# 06_-_CPU_-_HDMI_LVDS.net
KiCad netlist of a schematic drawn in Altium Designer
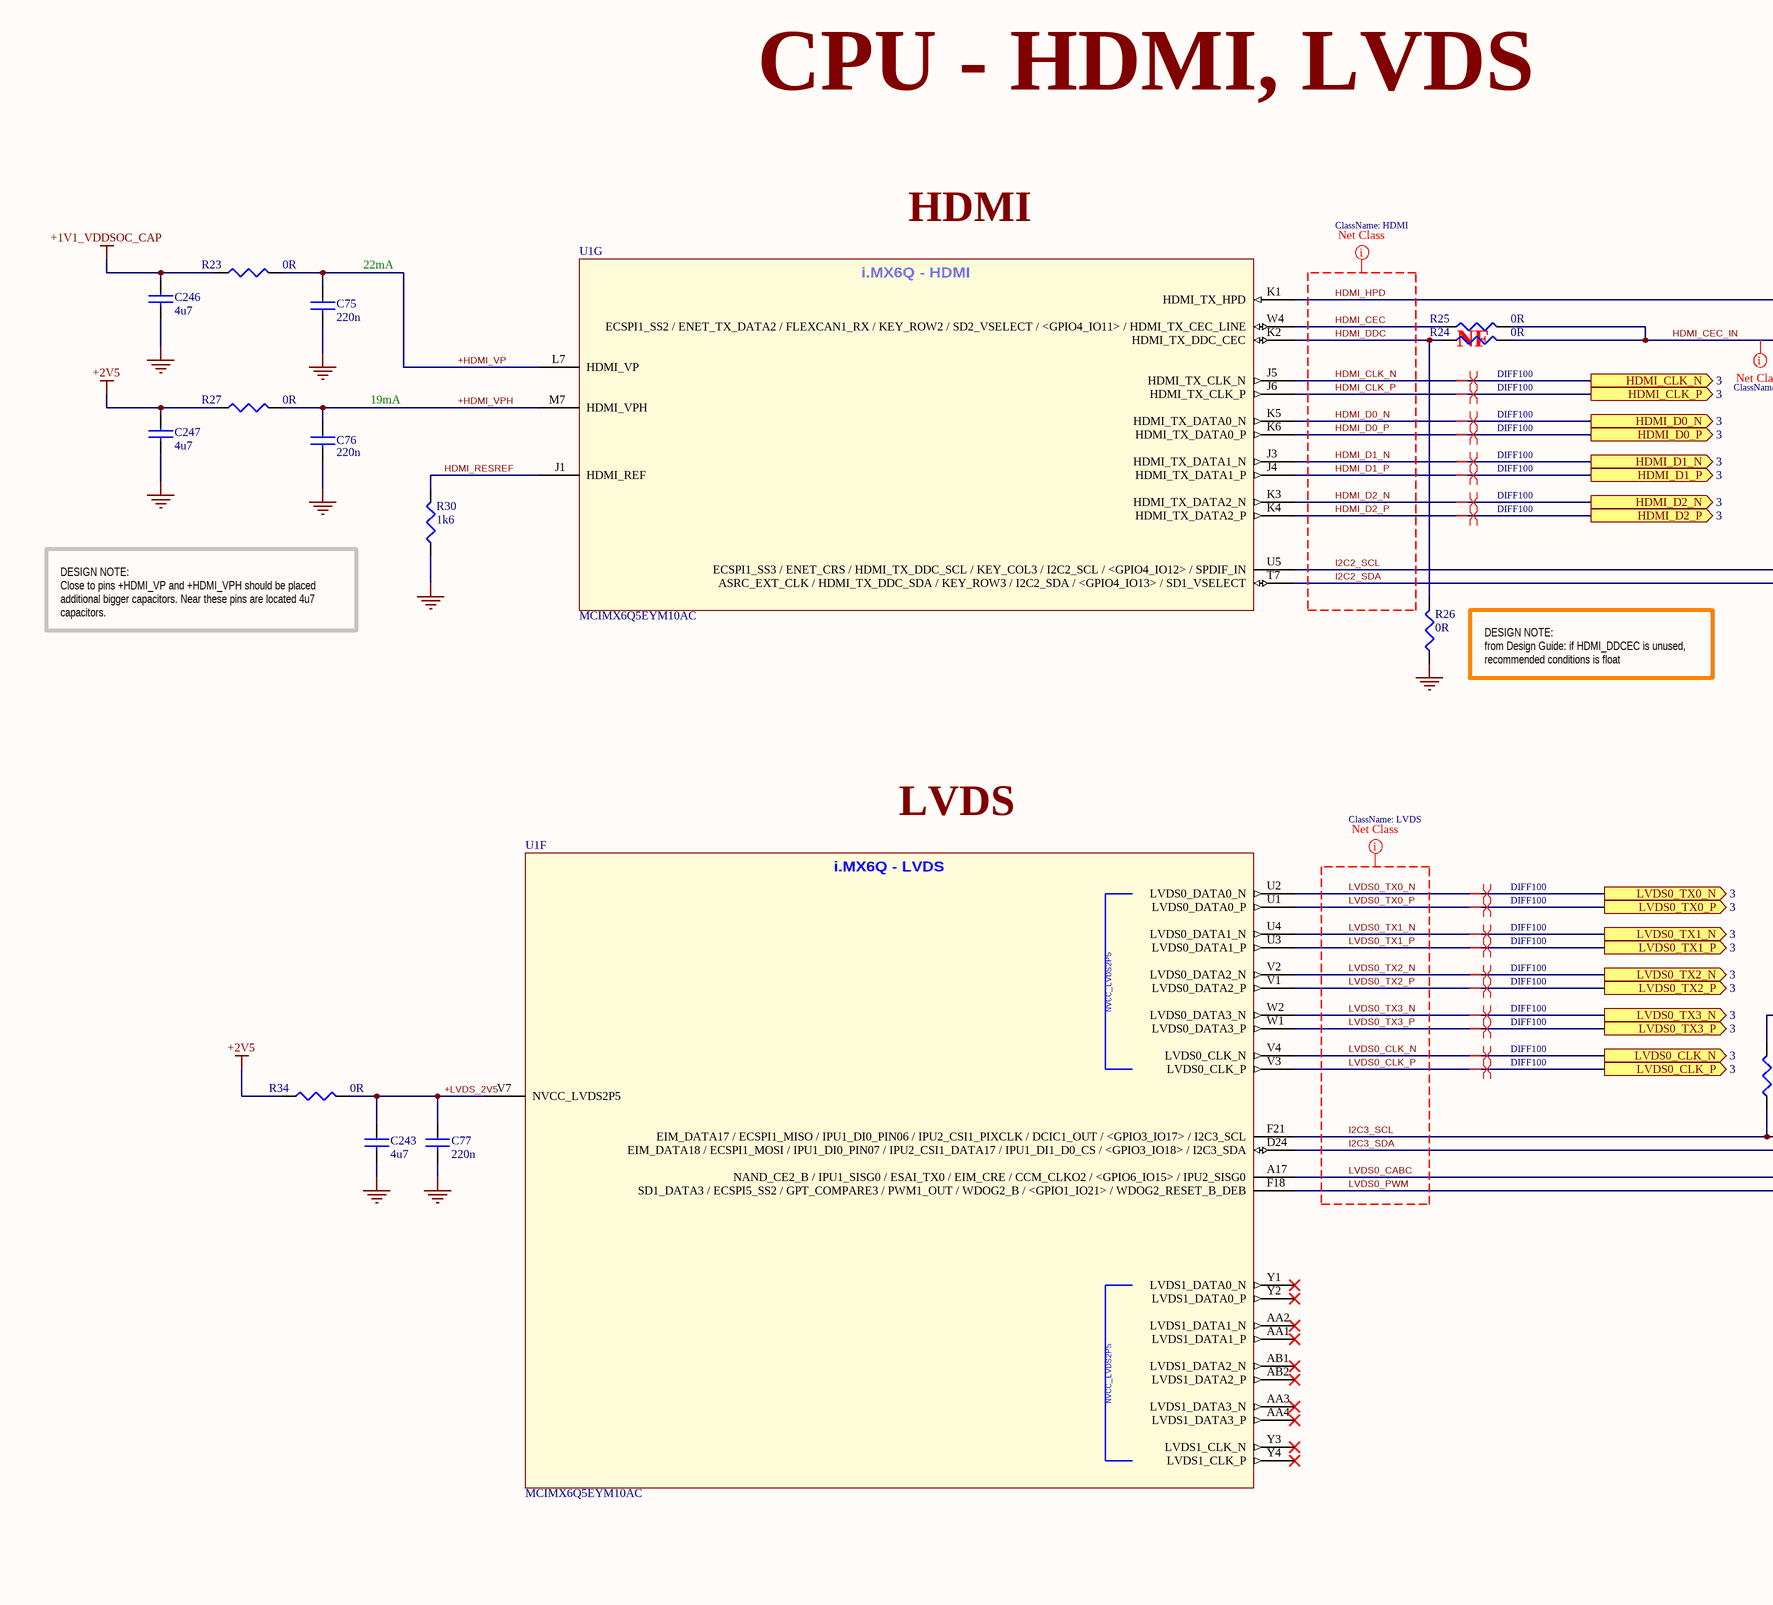
[diagram p0: [06] - CPU - HDMI, LVDS.SchDoc, left]
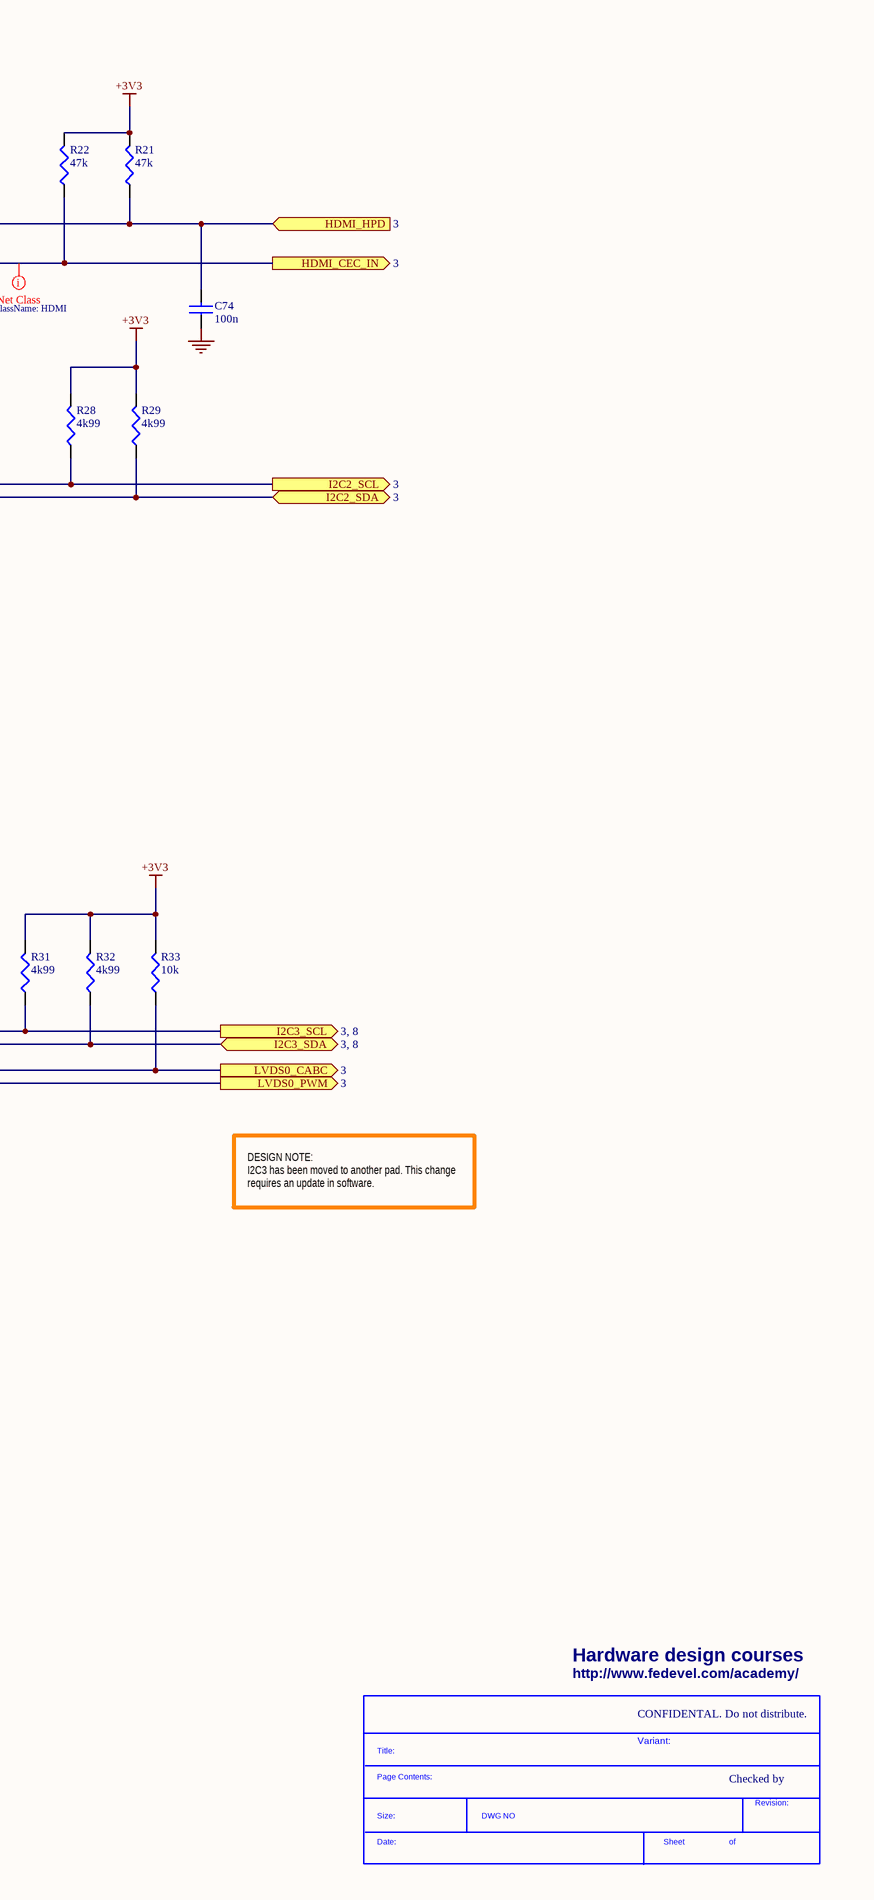
[diagram p1: [06] - CPU - HDMI, LVDS.SchDoc, right]

(export (version "E")
  (design (tool "Eeschema 10.0.6"))
  (components
    (comp (ref "C74")
      (value "100n")
      (footprint "C0402")
      (description "CAP CER .10UF 50V X5R 10% 0402")
      (fields
        (field (name "MANUFACTURER") "TDK Corporation")
        (field (name "MANUFACTURER PART NUMBER") "C1005X5R1H104K")
      )
      (libsource (lib "Integrated_Library_RF_FEB_2012") (part "C1005X5R1H104K"))
    )
    (comp (ref "C75")
      (value "220n")
      (footprint "C0402")
      (description "CAP CER .22UF 25V X5R 20% 0402")
      (fields
        (field (name "MANUFACTURER") "TDK Corporation")
        (field (name "MANUFACTURER PART NUMBER") "C1005X5R1E224M")
      )
      (libsource (lib "Integrated_Library_RF_FEB_2012") (part "C1005X5R1E224M"))
    )
    (comp (ref "C76")
      (value "220n")
      (footprint "C0402")
      (description "CAP CER .22UF 25V X5R 20% 0402")
      (fields
        (field (name "MANUFACTURER") "TDK Corporation")
        (field (name "MANUFACTURER PART NUMBER") "C1005X5R1E224M")
      )
      (libsource (lib "Integrated_Library_RF_FEB_2012") (part "C1005X5R1E224M"))
    )
    (comp (ref "C77")
      (value "220n")
      (footprint "C0402")
      (description "CAP CER .22UF 25V X5R 20% 0402")
      (fields
        (field (name "MANUFACTURER") "TDK Corporation")
        (field (name "MANUFACTURER PART NUMBER") "C1005X5R1E224M")
      )
      (libsource (lib "Integrated_Library_RF_FEB_2012") (part "C1005X5R1E224M"))
    )
    (comp (ref "C243")
      (value "4u7")
      (footprint "C0402")
      (description "CAP CER 4.7UF 10V 20% X5R 0402")
      (fields
        (field (name "MANUFACTURER") "TDK Corporation")
        (field (name "MANUFACTURER PART NUMBER") "C1005X5R1A475M")
        (field (name ".CHECKED PCB") "RF")
        (field (name ".CHECKED SCH") "RF")
      )
      (libsource (lib "Integrated_Library_RF_FEB_2012") (part "C1005X5R1A475M"))
    )
    (comp (ref "C246")
      (value "4u7")
      (footprint "C0402")
      (description "CAP CER 4.7UF 10V 20% X5R 0402")
      (fields
        (field (name "MANUFACTURER") "TDK Corporation")
        (field (name "MANUFACTURER PART NUMBER") "C1005X5R1A475M")
        (field (name ".CHECKED PCB") "RF")
        (field (name ".CHECKED SCH") "RF")
      )
      (libsource (lib "Integrated_Library_RF_FEB_2012") (part "C1005X5R1A475M"))
    )
    (comp (ref "C247")
      (value "4u7")
      (footprint "C0402")
      (description "CAP CER 4.7UF 10V 20% X5R 0402")
      (fields
        (field (name "MANUFACTURER") "TDK Corporation")
        (field (name "MANUFACTURER PART NUMBER") "C1005X5R1A475M")
        (field (name ".CHECKED PCB") "RF")
        (field (name ".CHECKED SCH") "RF")
      )
      (libsource (lib "Integrated_Library_RF_FEB_2012") (part "C1005X5R1A475M"))
    )
    (comp (ref "R21")
      (value "47k")
      (footprint "R0402")
      (description "RES 47.0K OHM 1/16W 1% 0402 SMD")
      (fields
        (field (name "MANUFACTURER") "Yageo")
        (field (name "MANUFACTURER PART NUMBER") "RC0402FR-0747KL")
      )
      (libsource (lib "Integrated_Library_RF_FEB_2012") (part "RC0402FR-0747KL"))
    )
    (comp (ref "R22")
      (value "47k")
      (footprint "R0402")
      (description "RES 47.0K OHM 1/16W 1% 0402 SMD")
      (fields
        (field (name "MANUFACTURER") "Yageo")
        (field (name "MANUFACTURER PART NUMBER") "RC0402FR-0747KL")
      )
      (libsource (lib "Integrated_Library_RF_FEB_2012") (part "RC0402FR-0747KL"))
    )
    (comp (ref "R23")
      (value "0R")
      (footprint "R0402")
      (description "RES 0.0 OHM 1/16W 0402 SMD")
      (fields
        (field (name "MANUFACTURER") "Yageo")
        (field (name "MANUFACTURER PART NUMBER") "RC0402JR-070RL")
      )
      (libsource (lib "Integrated_Library_RF_FEB_2012") (part "RC0402JR-070RL"))
    )
    (comp (ref "R24")
      (value "0R")
      (footprint "R0402")
      (description "RES 0.0 OHM 1/16W 0402 SMD")
      (fields
        (field (name "MANUFACTURER") "Yageo")
        (field (name "MANUFACTURER PART NUMBER") "RC0402JR-070RL")
      )
      (libsource (lib "Integrated_Library_RF_FEB_2012") (part "RC0402JR-070RL"))
    )
    (comp (ref "R25")
      (value "0R")
      (footprint "R0402")
      (description "RES 0.0 OHM 1/16W 0402 SMD")
      (fields
        (field (name "MANUFACTURER") "Yageo")
        (field (name "MANUFACTURER PART NUMBER") "RC0402JR-070RL")
      )
      (libsource (lib "Integrated_Library_RF_FEB_2012") (part "RC0402JR-070RL"))
    )
    (comp (ref "R26")
      (value "0R")
      (footprint "R0402")
      (description "RES 0.0 OHM 1/16W 0402 SMD")
      (fields
        (field (name "MANUFACTURER") "Yageo")
        (field (name "MANUFACTURER PART NUMBER") "RC0402JR-070RL")
      )
      (libsource (lib "Integrated_Library_RF_FEB_2012") (part "RC0402JR-070RL"))
    )
    (comp (ref "R27")
      (value "0R")
      (footprint "R0402")
      (description "RES 0.0 OHM 1/16W 0402 SMD")
      (fields
        (field (name "MANUFACTURER") "Yageo")
        (field (name "MANUFACTURER PART NUMBER") "RC0402JR-070RL")
      )
      (libsource (lib "Integrated_Library_RF_FEB_2012") (part "RC0402JR-070RL"))
    )
    (comp (ref "R28")
      (value "4k99")
      (footprint "R0402")
      (description "RES TF 4.99K OHM 1% 1/16W 0402")
      (fields
        (field (name "MANUFACTURER") "Stackpole Electronics Inc")
        (field (name "MANUFACTURER PART NUMBER") "RMCF0402FT4K99")
      )
      (libsource (lib "Integrated_Library_RF_FEB_2012") (part "RMCF0402FT4K99"))
    )
    (comp (ref "R29")
      (value "4k99")
      (footprint "R0402")
      (description "RES TF 4.99K OHM 1% 1/16W 0402")
      (fields
        (field (name "MANUFACTURER") "Stackpole Electronics Inc")
        (field (name "MANUFACTURER PART NUMBER") "RMCF0402FT4K99")
      )
      (libsource (lib "Integrated_Library_RF_FEB_2012") (part "RMCF0402FT4K99"))
    )
    (comp (ref "R30")
      (value "1k6")
      (footprint "R0402")
      (description "RES 1.6K OHM 1/10W 1% 0402 SMD")
      (fields
        (field (name "MANUFACTURER") "Panasonic Electronic Components")
        (field (name "MANUFACTURER PART NUMBER") "ERJ-2RKF1601X")
        (field (name ".CREATOR") "MM")
        (field (name ".CHECKED PCB") "RF, used by MM")
        (field (name ".CHECKED SCH") "MM, checked by RF")
      )
      (libsource (lib "Schlib_RF") (part "ERJ-2RKF1601X"))
    )
    (comp (ref "R31")
      (value "4k99")
      (footprint "R0402")
      (description "RES TF 4.99K OHM 1% 1/16W 0402")
      (fields
        (field (name "MANUFACTURER") "Stackpole Electronics Inc")
        (field (name "MANUFACTURER PART NUMBER") "RMCF0402FT4K99")
      )
      (libsource (lib "Integrated_Library_RF_FEB_2012") (part "RMCF0402FT4K99"))
    )
    (comp (ref "R32")
      (value "4k99")
      (footprint "R0402")
      (description "RES TF 4.99K OHM 1% 1/16W 0402")
      (fields
        (field (name "MANUFACTURER") "Stackpole Electronics Inc")
        (field (name "MANUFACTURER PART NUMBER") "RMCF0402FT4K99")
      )
      (libsource (lib "Integrated_Library_RF_FEB_2012") (part "RMCF0402FT4K99"))
    )
    (comp (ref "R33")
      (value "10k")
      (footprint "R0402")
      (description "RES 10.0K OHM 1/16W 1% 0402 SMD")
      (fields
        (field (name "MANUFACTURER") "Yageo")
        (field (name "MANUFACTURER PART NUMBER") "RC0402FR-0710KL")
      )
      (libsource (lib "Integrated_Library_RF_FEB_2012") (part "RC0402FR-0710KL"))
    )
    (comp (ref "R34")
      (value "0R")
      (footprint "R0402")
      (description "RES 0.0 OHM 1/16W 0402 SMD")
      (fields
        (field (name "MANUFACTURER") "Yageo")
        (field (name "MANUFACTURER PART NUMBER") "RC0402JR-070RL")
      )
      (libsource (lib "Integrated_Library_RF_FEB_2012") (part "RC0402JR-070RL"))
    )
    (comp (ref "U1")
      (value "MCIMX6Q5EYM10AC")
      (footprint "PBGA624")
      (description "IC MCU 32BIT ARM QUAD 624FCBGA")
      (fields
        (field (name "MANUFACTURER") "Freescale Semiconductor")
        (field (name ".CREATOR") "MM")
        (field (name ".CHECKED PCB") "MM, checked by RF")
        (field (name ".CHECKED SCH") "MM")
      )
      (libsource (lib "Schlib_RF") (part "MCIMX6Q5EYM10AC"))
    )
  )
  (nets
    (net (code "1") (name "+1V1_VDDSOC_CAP") (class "Default")
      (node (ref "C246") (pin "1") (pinfunction "1_1") (pintype "passive"))
      (node (ref "R23") (pin "1") (pinfunction "1_1") (pintype "passive"))
    )
    (net (code "2") (name "+2V5") (class "Default")
      (node (ref "C247") (pin "1") (pinfunction "1_1") (pintype "passive"))
      (node (ref "R27") (pin "1") (pinfunction "1_1") (pintype "passive"))
      (node (ref "R34") (pin "1") (pinfunction "1_1") (pintype "passive"))
    )
    (net (code "3") (name "+3V3") (class "Default")
      (node (ref "R21") (pin "2") (pinfunction "2_2") (pintype "passive"))
      (node (ref "R22") (pin "2") (pinfunction "2_2") (pintype "passive"))
      (node (ref "R28") (pin "2") (pinfunction "2_2") (pintype "passive"))
      (node (ref "R29") (pin "2") (pinfunction "2_2") (pintype "passive"))
      (node (ref "R31") (pin "2") (pinfunction "2_2") (pintype "passive"))
      (node (ref "R32") (pin "2") (pinfunction "2_2") (pintype "passive"))
      (node (ref "R33") (pin "2") (pinfunction "2_2") (pintype "passive"))
    )
    (net (code "4") (name "/+HDMI_VP") (class "Default")
      (node (ref "C75") (pin "1") (pinfunction "1_1") (pintype "passive"))
      (node (ref "R23") (pin "2") (pinfunction "2_2") (pintype "passive"))
      (node (ref "U1") (pin "L7") (pinfunction "HDMI_VP_L7") (pintype "power_in"))
    )
    (net (code "5") (name "/+HDMI_VPH") (class "Default")
      (node (ref "C76") (pin "1") (pinfunction "1_1") (pintype "passive"))
      (node (ref "R27") (pin "2") (pinfunction "2_2") (pintype "passive"))
      (node (ref "U1") (pin "M7") (pinfunction "HDMI_VPH_M7") (pintype "power_in"))
    )
    (net (code "6") (name "/+LVDS_2V5") (class "Default")
      (node (ref "C243") (pin "1") (pinfunction "1_1") (pintype "passive"))
      (node (ref "C77") (pin "1") (pinfunction "1_1") (pintype "passive"))
      (node (ref "R34") (pin "2") (pinfunction "2_2") (pintype "passive"))
      (node (ref "U1") (pin "V7") (pinfunction "NVCC_LVDS2P5_V7") (pintype "power_in"))
    )
    (net (code "7") (name "/HDMI_CEC") (class "Default")
      (node (ref "R25") (pin "1") (pinfunction "1_1") (pintype "passive"))
      (node (ref "U1") (pin "W4") (pinfunction "ECSPI1_SS2_/_ENET_TX_DATA2_/_FLEXCAN1_RX_/_KEY_ROW2_/_SD2_VSELECT_/_<GPIO4_IO11>_/_HDMI_TX_CEC_LINE_W4") (pintype "bidirectional"))
    )
    (net (code "8") (name "/HDMI_CEC_IN") (class "Default")
      (node (ref "R22") (pin "1") (pinfunction "1_1") (pintype "passive"))
      (node (ref "R24") (pin "2") (pinfunction "2_2") (pintype "passive"))
      (node (ref "R25") (pin "2") (pinfunction "2_2") (pintype "passive"))
    )
    (net (code "9") (name "/HDMI_CLK_N") (class "Default")
      (node (ref "U1") (pin "J5") (pinfunction "HDMI_TX_CLK_N_J5") (pintype "output"))
    )
    (net (code "10") (name "/HDMI_CLK_P") (class "Default")
      (node (ref "U1") (pin "J6") (pinfunction "HDMI_TX_CLK_P_J6") (pintype "output"))
    )
    (net (code "11") (name "/HDMI_D0_N") (class "Default")
      (node (ref "U1") (pin "K5") (pinfunction "HDMI_TX_DATA0_N_K5") (pintype "output"))
    )
    (net (code "12") (name "/HDMI_D0_P") (class "Default")
      (node (ref "U1") (pin "K6") (pinfunction "HDMI_TX_DATA0_P_K6") (pintype "output"))
    )
    (net (code "13") (name "/HDMI_D1_N") (class "Default")
      (node (ref "U1") (pin "J3") (pinfunction "HDMI_TX_DATA1_N_J3") (pintype "output"))
    )
    (net (code "14") (name "/HDMI_D1_P") (class "Default")
      (node (ref "U1") (pin "J4") (pinfunction "HDMI_TX_DATA1_P_J4") (pintype "output"))
    )
    (net (code "15") (name "/HDMI_D2_N") (class "Default")
      (node (ref "U1") (pin "K3") (pinfunction "HDMI_TX_DATA2_N_K3") (pintype "output"))
    )
    (net (code "16") (name "/HDMI_D2_P") (class "Default")
      (node (ref "U1") (pin "K4") (pinfunction "HDMI_TX_DATA2_P_K4") (pintype "output"))
    )
    (net (code "17") (name "/HDMI_DDC") (class "Default")
      (node (ref "R24") (pin "1") (pinfunction "1_1") (pintype "passive"))
      (node (ref "R26") (pin "2") (pinfunction "2_2") (pintype "passive"))
      (node (ref "U1") (pin "K2") (pinfunction "HDMI_TX_DDC_CEC_K2") (pintype "bidirectional"))
    )
    (net (code "18") (name "/HDMI_HPD") (class "Default")
      (node (ref "C74") (pin "2") (pinfunction "2_2") (pintype "passive"))
      (node (ref "R21") (pin "1") (pinfunction "1_1") (pintype "passive"))
      (node (ref "U1") (pin "K1") (pinfunction "HDMI_TX_HPD_K1") (pintype "input"))
    )
    (net (code "19") (name "/HDMI_RESREF") (class "Default")
      (node (ref "R30") (pin "2") (pinfunction "2_2") (pintype "passive"))
      (node (ref "U1") (pin "J1") (pinfunction "HDMI_REF_J1") (pintype "passive"))
    )
    (net (code "20") (name "/I2C2_SCL") (class "Default")
      (node (ref "R28") (pin "1") (pinfunction "1_1") (pintype "passive"))
      (node (ref "U1") (pin "U5") (pinfunction "ECSPI1_SS3_/_ENET_CRS_/_HDMI_TX_DDC_SCL_/_KEY_COL3_/_I2C2_SCL_/_<GPIO4_IO12>_/_SPDIF_IN_U5") (pintype "passive"))
    )
    (net (code "21") (name "/I2C2_SDA") (class "Default")
      (node (ref "R29") (pin "1") (pinfunction "1_1") (pintype "passive"))
      (node (ref "U1") (pin "T7") (pinfunction "ASRC_EXT_CLK_/_HDMI_TX_DDC_SDA_/_KEY_ROW3_/_I2C2_SDA_/_<GPIO4_IO13>_/_SD1_VSELECT_T7") (pintype "bidirectional"))
    )
    (net (code "22") (name "/I2C3_SCL") (class "Default")
      (node (ref "R31") (pin "1") (pinfunction "1_1") (pintype "passive"))
      (node (ref "U1") (pin "F21") (pinfunction "EIM_DATA17_/_ECSPI1_MISO_/_IPU1_DI0_PIN06_/_IPU2_CSI1_PIXCLK_/_DCIC1_OUT_/_<GPIO3_IO17>_/_I2C3_SCL_F21") (pintype "passive"))
    )
    (net (code "23") (name "/I2C3_SDA") (class "Default")
      (node (ref "R32") (pin "1") (pinfunction "1_1") (pintype "passive"))
      (node (ref "U1") (pin "D24") (pinfunction "EIM_DATA18_/_ECSPI1_MOSI_/_IPU1_DI0_PIN07_/_IPU2_CSI1_DATA17_/_IPU1_DI1_D0_CS_/_<GPIO3_IO18>_/_I2C3_SDA_D24") (pintype "bidirectional"))
    )
    (net (code "24") (name "/LVDS0_CABC") (class "Default")
      (node (ref "R33") (pin "1") (pinfunction "1_1") (pintype "passive"))
      (node (ref "U1") (pin "A17") (pinfunction "NAND_CE2_B_/_IPU1_SISG0_/_ESAI_TX0_/_EIM_CRE_/_CCM_CLKO2_/_<GPIO6_IO15>_/_IPU2_SISG0_A17") (pintype "passive"))
    )
    (net (code "25") (name "/LVDS0_CLK_N") (class "Default")
      (node (ref "U1") (pin "V4") (pinfunction "LVDS0_CLK_N_V4") (pintype "output"))
    )
    (net (code "26") (name "/LVDS0_CLK_P") (class "Default")
      (node (ref "U1") (pin "V3") (pinfunction "LVDS0_CLK_P_V3") (pintype "output"))
    )
    (net (code "27") (name "/LVDS0_PWM") (class "Default")
      (node (ref "U1") (pin "F18") (pinfunction "SD1_DATA3_/_ECSPI5_SS2_/_GPT_COMPARE3_/_PWM1_OUT_/_WDOG2_B_/_<GPIO1_IO21>_/_WDOG2_RESET_B_DEB_F18") (pintype "passive"))
    )
    (net (code "28") (name "/LVDS0_TX0_N") (class "Default")
      (node (ref "U1") (pin "U2") (pinfunction "LVDS0_DATA0_N_U2") (pintype "output"))
    )
    (net (code "29") (name "/LVDS0_TX0_P") (class "Default")
      (node (ref "U1") (pin "U1") (pinfunction "LVDS0_DATA0_P_U1") (pintype "output"))
    )
    (net (code "30") (name "/LVDS0_TX1_N") (class "Default")
      (node (ref "U1") (pin "U4") (pinfunction "LVDS0_DATA1_N_U4") (pintype "output"))
    )
    (net (code "31") (name "/LVDS0_TX1_P") (class "Default")
      (node (ref "U1") (pin "U3") (pinfunction "LVDS0_DATA1_P_U3") (pintype "output"))
    )
    (net (code "32") (name "/LVDS0_TX2_N") (class "Default")
      (node (ref "U1") (pin "V2") (pinfunction "LVDS0_DATA2_N_V2") (pintype "output"))
    )
    (net (code "33") (name "/LVDS0_TX2_P") (class "Default")
      (node (ref "U1") (pin "V1") (pinfunction "LVDS0_DATA2_P_V1") (pintype "output"))
    )
    (net (code "34") (name "/LVDS0_TX3_N") (class "Default")
      (node (ref "U1") (pin "W2") (pinfunction "LVDS0_DATA3_N_W2") (pintype "output"))
    )
    (net (code "35") (name "/LVDS0_TX3_P") (class "Default")
      (node (ref "U1") (pin "W1") (pinfunction "LVDS0_DATA3_P_W1") (pintype "output"))
    )
    (net (code "36") (name "GND") (class "Default")
      (node (ref "C243") (pin "2") (pinfunction "2_2") (pintype "passive"))
      (node (ref "C246") (pin "2") (pinfunction "2_2") (pintype "passive"))
      (node (ref "C247") (pin "2") (pinfunction "2_2") (pintype "passive"))
      (node (ref "C74") (pin "1") (pinfunction "1_1") (pintype "passive"))
      (node (ref "C75") (pin "2") (pinfunction "2_2") (pintype "passive"))
      (node (ref "C76") (pin "2") (pinfunction "2_2") (pintype "passive"))
      (node (ref "C77") (pin "2") (pinfunction "2_2") (pintype "passive"))
      (node (ref "R26") (pin "1") (pinfunction "1_1") (pintype "passive"))
      (node (ref "R30") (pin "1") (pinfunction "1_1") (pintype "passive"))
    )
    (net (code "37") (name "unconnected-(U1F-LVDS1_CLK_N-PadY3)") (class "Default")
      (node (ref "U1") (pin "Y3") (pinfunction "LVDS1_CLK_N_Y3") (pintype "output+no_connect"))
    )
    (net (code "38") (name "unconnected-(U1F-LVDS1_CLK_P-PadY4)") (class "Default")
      (node (ref "U1") (pin "Y4") (pinfunction "LVDS1_CLK_P_Y4") (pintype "output+no_connect"))
    )
    (net (code "39") (name "unconnected-(U1F-LVDS1_DATA0_N-PadY1)") (class "Default")
      (node (ref "U1") (pin "Y1") (pinfunction "LVDS1_DATA0_N_Y1") (pintype "output+no_connect"))
    )
    (net (code "40") (name "unconnected-(U1F-LVDS1_DATA0_P-PadY2)") (class "Default")
      (node (ref "U1") (pin "Y2") (pinfunction "LVDS1_DATA0_P_Y2") (pintype "output+no_connect"))
    )
    (net (code "41") (name "unconnected-(U1F-LVDS1_DATA1_N-PadAA2)") (class "Default")
      (node (ref "U1") (pin "AA2") (pinfunction "LVDS1_DATA1_N_AA2") (pintype "output+no_connect"))
    )
    (net (code "42") (name "unconnected-(U1F-LVDS1_DATA1_P-PadAA1)") (class "Default")
      (node (ref "U1") (pin "AA1") (pinfunction "LVDS1_DATA1_P_AA1") (pintype "output+no_connect"))
    )
    (net (code "43") (name "unconnected-(U1F-LVDS1_DATA2_N-PadAB1)") (class "Default")
      (node (ref "U1") (pin "AB1") (pinfunction "LVDS1_DATA2_N_AB1") (pintype "output+no_connect"))
    )
    (net (code "44") (name "unconnected-(U1F-LVDS1_DATA2_P-PadAB2)") (class "Default")
      (node (ref "U1") (pin "AB2") (pinfunction "LVDS1_DATA2_P_AB2") (pintype "output+no_connect"))
    )
    (net (code "45") (name "unconnected-(U1F-LVDS1_DATA3_N-PadAA3)") (class "Default")
      (node (ref "U1") (pin "AA3") (pinfunction "LVDS1_DATA3_N_AA3") (pintype "output+no_connect"))
    )
    (net (code "46") (name "unconnected-(U1F-LVDS1_DATA3_P-PadAA4)") (class "Default")
      (node (ref "U1") (pin "AA4") (pinfunction "LVDS1_DATA3_P_AA4") (pintype "output+no_connect"))
    )
  )
)
